# 10scm153adp1_io.net
KiCad netlist of a schematic drawn in Altium Designer
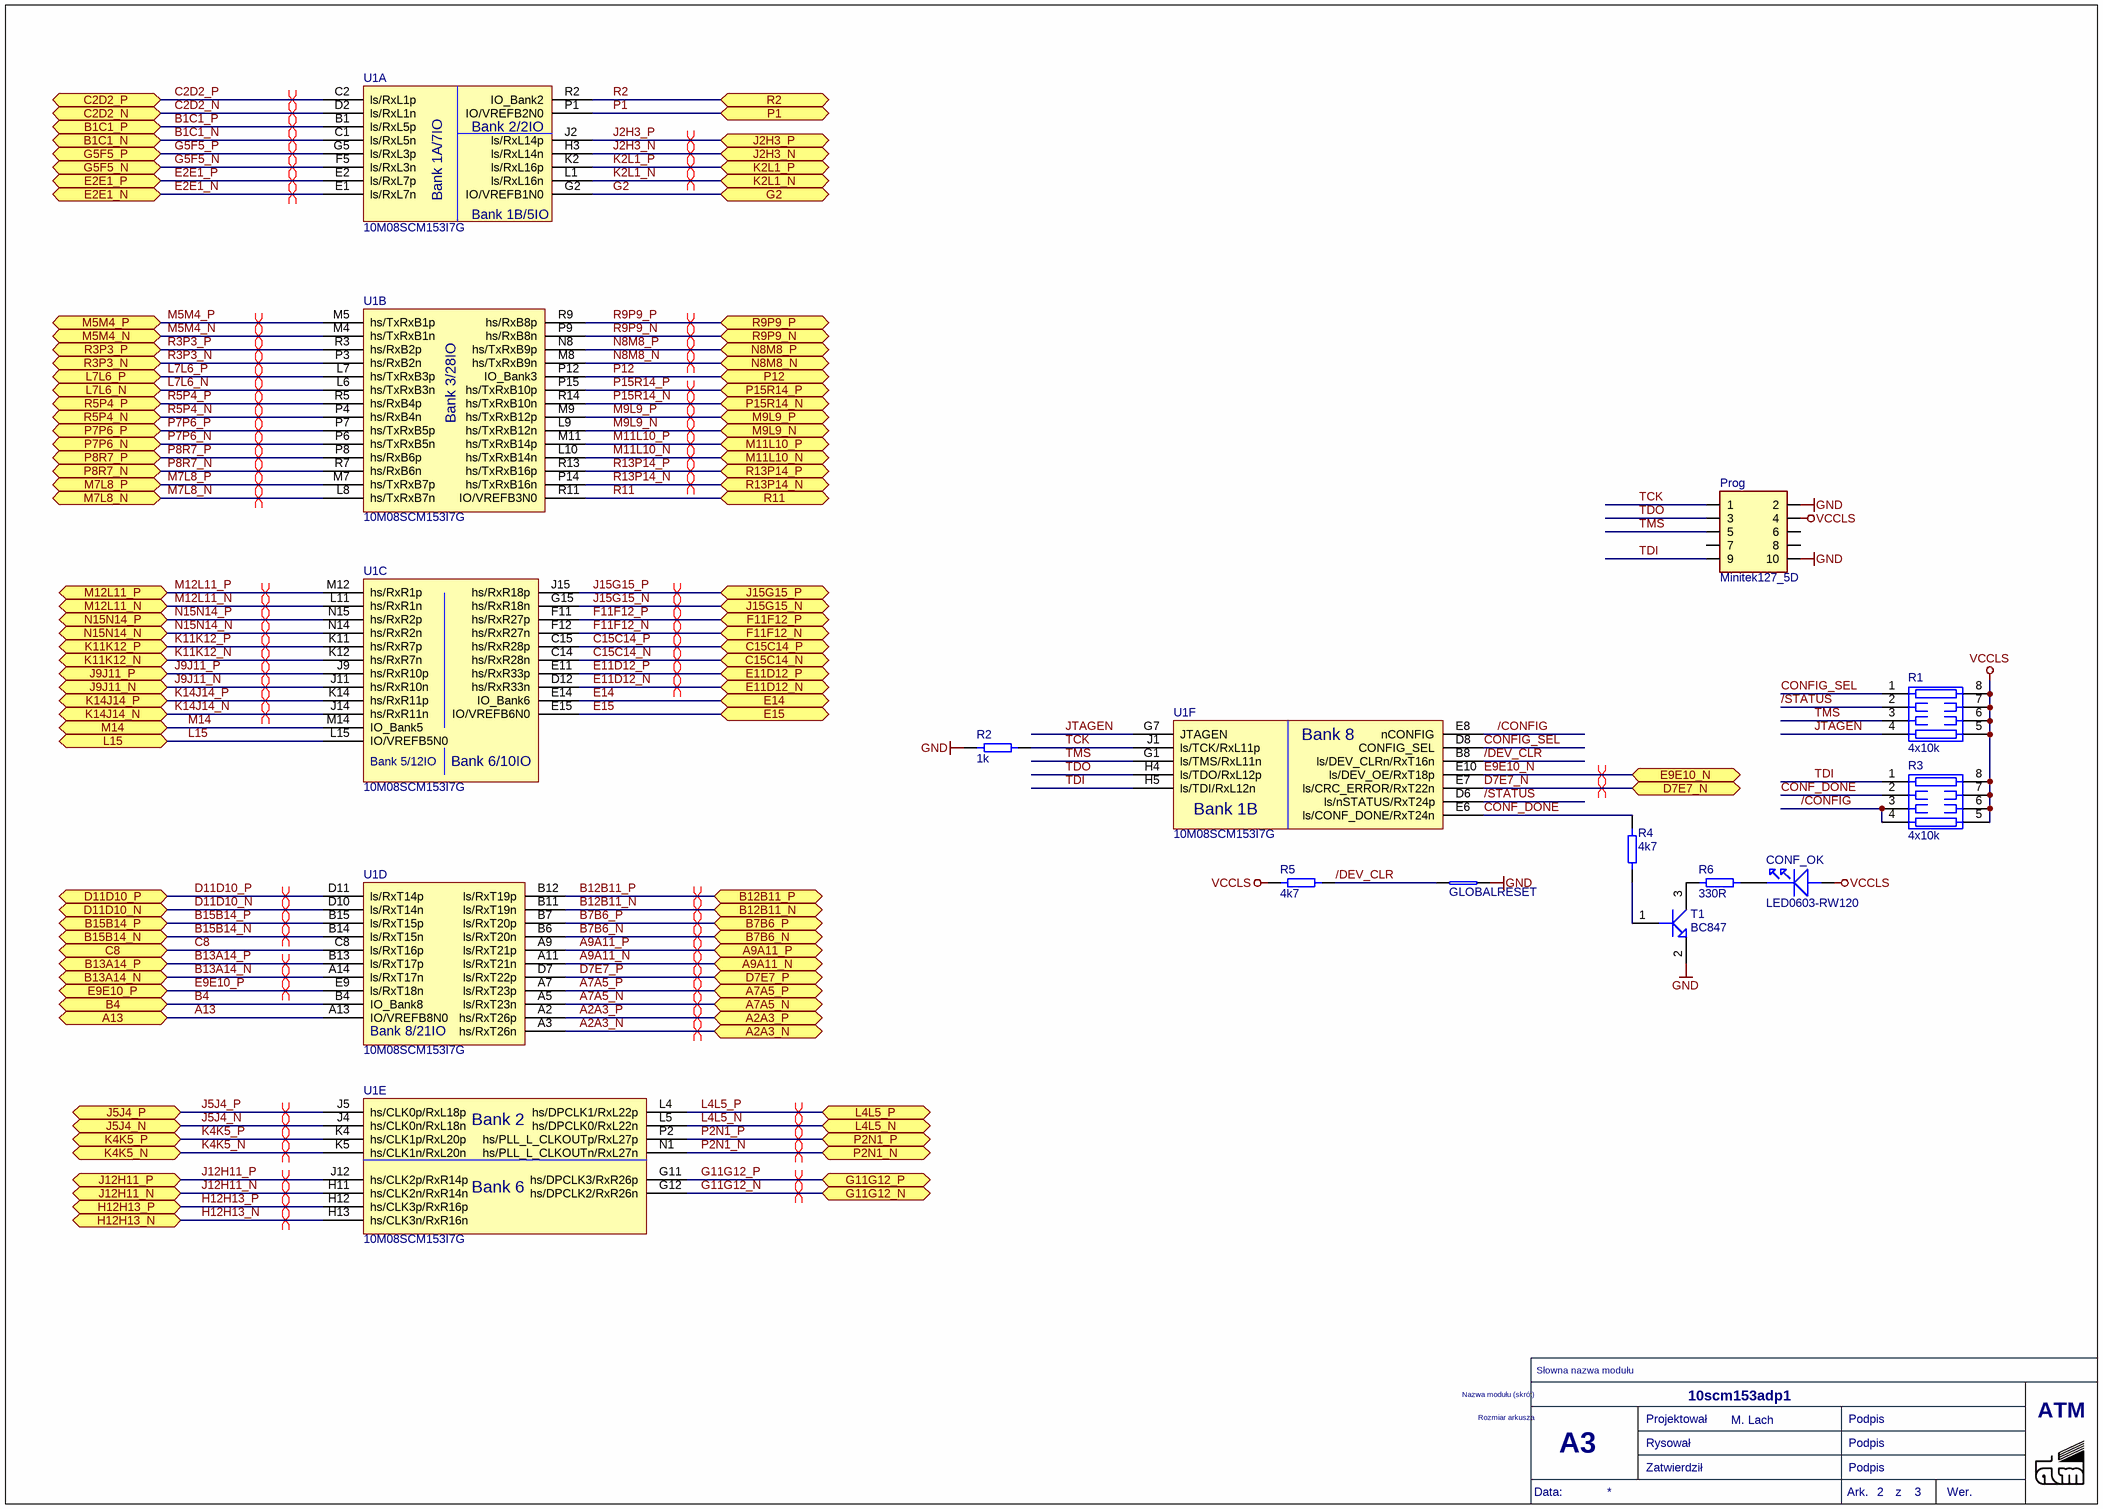
[diagram p0: 10scm153adp1_io.SchDoc]

(export (version "E")
  (design (tool "Eeschema 10.0.6"))
  (components
    (comp (ref "CONF_OK")
      (value "LED0603-RW120")
      (footprint "D0603")
      (libsource (lib "PartsMySQL") (part "LED"))
    )
    (comp (ref "GLOBALRESET")
      (value "SHORT0805")
      (footprint "SHORT0805")
      (libsource (lib "PartsMySQL") (part "SHORT"))
    )
    (comp (ref "Prog")
      (value "Minitek127_5D")
      (footprint "MINITEK127_5D")
      (libsource (lib "PartsMySQL") (part "HEADER5X2"))
    )
    (comp (ref "R1") (value "4x10k") (footprint "1206RP") (libsource (lib "PartsMySQL") (part "DR1206")))
    (comp (ref "R2") (value "1k") (footprint "0603R") (libsource (lib "PartsMySQL") (part "R")))
    (comp (ref "R3") (value "4x10k") (footprint "1206RP") (libsource (lib "PartsMySQL") (part "DR1206")))
    (comp (ref "R4") (value "4k7") (footprint "0603R") (libsource (lib "PartsMySQL") (part "R")))
    (comp (ref "R5") (value "4k7") (footprint "0603R") (libsource (lib "PartsMySQL") (part "R")))
    (comp (ref "R6") (value "330R") (footprint "0603R") (libsource (lib "PartsMySQL") (part "R")))
    (comp (ref "T1")
      (value "BC847")
      (footprint "SOT23-3")
      (libsource (lib "PartsMySQL") (part "NPN_SOT23-3"))
    )
    (comp (ref "U1")
      (value "10M08SCM153I7G")
      (footprint "MBGA153x15")
      (libsource (lib "PartsMySQL") (part "10M08SCM153"))
    )
  )
  (nets
    (net (code "1") (name "/A2A3_N") (class "Default")
      (node (ref "U1") (pin "A3") (pinfunction "hs/RxT26n_A3") (pintype "passive"))
    )
    (net (code "2") (name "/A2A3_P") (class "Default")
      (node (ref "U1") (pin "A2") (pinfunction "hs/RxT26p_A2") (pintype "passive"))
    )
    (net (code "3") (name "/A7A5_N") (class "Default")
      (node (ref "U1") (pin "A5") (pinfunction "ls/RxT23n_A5") (pintype "passive"))
    )
    (net (code "4") (name "/A7A5_P") (class "Default")
      (node (ref "U1") (pin "A7") (pinfunction "ls/RxT23p_A7") (pintype "passive"))
    )
    (net (code "5") (name "/A9A11_N") (class "Default")
      (node (ref "U1") (pin "A11") (pinfunction "ls/RxT21n_A11") (pintype "passive"))
    )
    (net (code "6") (name "/A9A11_P") (class "Default")
      (node (ref "U1") (pin "A9") (pinfunction "ls/RxT21p_A9") (pintype "passive"))
    )
    (net (code "7") (name "/A13") (class "Default")
      (node (ref "U1") (pin "A13") (pinfunction "IO/VREFB8N0_A13") (pintype "passive"))
    )
    (net (code "8") (name "/B1C1_N") (class "Default")
      (node (ref "U1") (pin "C1") (pinfunction "ls/RxL5n_C1") (pintype "passive"))
    )
    (net (code "9") (name "/B1C1_P") (class "Default")
      (node (ref "U1") (pin "B1") (pinfunction "ls/RxL5p_B1") (pintype "passive"))
    )
    (net (code "10") (name "/B4") (class "Default")
      (node (ref "U1") (pin "B4") (pinfunction "IO_Bank8_B4") (pintype "passive"))
    )
    (net (code "11") (name "/B7B6_N") (class "Default")
      (node (ref "U1") (pin "B6") (pinfunction "ls/RxT20n_B6") (pintype "passive"))
    )
    (net (code "12") (name "/B7B6_P") (class "Default")
      (node (ref "U1") (pin "B7") (pinfunction "ls/RxT20p_B7") (pintype "passive"))
    )
    (net (code "13") (name "/B12B11_N") (class "Default")
      (node (ref "U1") (pin "B11") (pinfunction "ls/RxT19n_B11") (pintype "passive"))
    )
    (net (code "14") (name "/B12B11_P") (class "Default")
      (node (ref "U1") (pin "B12") (pinfunction "ls/RxT19p_B12") (pintype "passive"))
    )
    (net (code "15") (name "/B13A14_N") (class "Default")
      (node (ref "U1") (pin "A14") (pinfunction "ls/RxT17n_A14") (pintype "passive"))
    )
    (net (code "16") (name "/B13A14_P") (class "Default")
      (node (ref "U1") (pin "B13") (pinfunction "ls/RxT17p_B13") (pintype "passive"))
    )
    (net (code "17") (name "/B15B14_N") (class "Default")
      (node (ref "U1") (pin "B14") (pinfunction "ls/RxT15n_B14") (pintype "passive"))
    )
    (net (code "18") (name "/B15B14_P") (class "Default")
      (node (ref "U1") (pin "B15") (pinfunction "ls/RxT15p_B15") (pintype "passive"))
    )
    (net (code "19") (name "/C2D2_N") (class "Default")
      (node (ref "U1") (pin "D2") (pinfunction "ls/RxL1n_D2") (pintype "passive"))
    )
    (net (code "20") (name "/C2D2_P") (class "Default")
      (node (ref "U1") (pin "C2") (pinfunction "ls/RxL1p_C2") (pintype "passive"))
    )
    (net (code "21") (name "/C8") (class "Default")
      (node (ref "U1") (pin "C8") (pinfunction "ls/RxT16p_C8") (pintype "passive"))
    )
    (net (code "22") (name "/C15C14_N") (class "Default")
      (node (ref "U1") (pin "C14") (pinfunction "hs/RxR28n_C14") (pintype "passive"))
    )
    (net (code "23") (name "/C15C14_P") (class "Default")
      (node (ref "U1") (pin "C15") (pinfunction "hs/RxR28p_C15") (pintype "passive"))
    )
    (net (code "24") (name "/CONFIG_SEL") (class "Default")
      (node (ref "R1") (pin "1") (pinfunction "R1_1") (pintype "passive"))
      (node (ref "U1") (pin "D8") (pinfunction "CONFIG_SEL_D8") (pintype "passive"))
    )
    (net (code "25") (name "/CONF_DONE") (class "Default")
      (node (ref "R3") (pin "2") (pinfunction "R2_2") (pintype "passive"))
      (node (ref "R4") (pin "1") (pinfunction "1_1") (pintype "passive"))
      (node (ref "U1") (pin "E6") (pinfunction "ls/CONF_DONE/RxT24n_E6") (pintype "passive"))
    )
    (net (code "26") (name "/D7E7_N") (class "Default")
      (node (ref "U1") (pin "E7") (pinfunction "ls/CRC_ERROR/RxT22n_E7") (pintype "passive"))
    )
    (net (code "27") (name "/D7E7_P") (class "Default")
      (node (ref "U1") (pin "D7") (pinfunction "ls/RxT22p_D7") (pintype "passive"))
    )
    (net (code "28") (name "/D11D10_N") (class "Default")
      (node (ref "U1") (pin "D10") (pinfunction "ls/RxT14n_D10") (pintype "passive"))
    )
    (net (code "29") (name "/D11D10_P") (class "Default")
      (node (ref "U1") (pin "D11") (pinfunction "ls/RxT14p_D11") (pintype "passive"))
    )
    (net (code "30") (name "/E2E1_N") (class "Default")
      (node (ref "U1") (pin "E1") (pinfunction "ls/RxL7n_E1") (pintype "passive"))
    )
    (net (code "31") (name "/E2E1_P") (class "Default")
      (node (ref "U1") (pin "E2") (pinfunction "ls/RxL7p_E2") (pintype "passive"))
    )
    (net (code "32") (name "/E9E10_N") (class "Default")
      (node (ref "U1") (pin "E10") (pinfunction "ls/DEV_OE/RxT18p_E10") (pintype "passive"))
    )
    (net (code "33") (name "/E9E10_P") (class "Default")
      (node (ref "U1") (pin "E9") (pinfunction "ls/RxT18n_E9") (pintype "passive"))
    )
    (net (code "34") (name "/E11D12_N") (class "Default")
      (node (ref "U1") (pin "D12") (pinfunction "hs/RxR33n_D12") (pintype "passive"))
    )
    (net (code "35") (name "/E11D12_P") (class "Default")
      (node (ref "U1") (pin "E11") (pinfunction "hs/RxR33p_E11") (pintype "passive"))
    )
    (net (code "36") (name "/E14") (class "Default")
      (node (ref "U1") (pin "E14") (pinfunction "IO_Bank6_E14") (pintype "passive"))
    )
    (net (code "37") (name "/E15") (class "Default")
      (node (ref "U1") (pin "E15") (pinfunction "IO/VREFB6N0_E15") (pintype "passive"))
    )
    (net (code "38") (name "/F11F12_N") (class "Default")
      (node (ref "U1") (pin "F12") (pinfunction "hs/RxR27n_F12") (pintype "passive"))
    )
    (net (code "39") (name "/F11F12_P") (class "Default")
      (node (ref "U1") (pin "F11") (pinfunction "hs/RxR27p_F11") (pintype "passive"))
    )
    (net (code "40") (name "/G2") (class "Default")
      (node (ref "U1") (pin "G2") (pinfunction "IO/VREFB1N0_G2") (pintype "passive"))
    )
    (net (code "41") (name "/G5F5_N") (class "Default")
      (node (ref "U1") (pin "F5") (pinfunction "ls/RxL3n_F5") (pintype "passive"))
    )
    (net (code "42") (name "/G5F5_P") (class "Default")
      (node (ref "U1") (pin "G5") (pinfunction "ls/RxL3p_G5") (pintype "passive"))
    )
    (net (code "43") (name "/G11G12_N") (class "Default")
      (node (ref "U1") (pin "G12") (pinfunction "hs/DPCLK2/RxR26n_G12") (pintype "passive"))
    )
    (net (code "44") (name "/G11G12_P") (class "Default")
      (node (ref "U1") (pin "G11") (pinfunction "hs/DPCLK3/RxR26p_G11") (pintype "passive"))
    )
    (net (code "45") (name "/H12H13_N") (class "Default")
      (node (ref "U1") (pin "H13") (pinfunction "hs/CLK3n/RxR16n_H13") (pintype "passive"))
    )
    (net (code "46") (name "/H12H13_P") (class "Default")
      (node (ref "U1") (pin "H12") (pinfunction "hs/CLK3p/RxR16p_H12") (pintype "passive"))
    )
    (net (code "47") (name "/J2H3_N") (class "Default")
      (node (ref "U1") (pin "H3") (pinfunction "ls/RxL14n_H3") (pintype "passive"))
    )
    (net (code "48") (name "/J2H3_P") (class "Default")
      (node (ref "U1") (pin "J2") (pinfunction "ls/RxL14p_J2") (pintype "passive"))
    )
    (net (code "49") (name "/J5J4_N") (class "Default")
      (node (ref "U1") (pin "J4") (pinfunction "hs/CLK0n/RxL18n_J4") (pintype "passive"))
    )
    (net (code "50") (name "/J5J4_P") (class "Default")
      (node (ref "U1") (pin "J5") (pinfunction "hs/CLK0p/RxL18p_J5") (pintype "passive"))
    )
    (net (code "51") (name "/J9J11_N") (class "Default")
      (node (ref "U1") (pin "J11") (pinfunction "hs/RxR10n_J11") (pintype "passive"))
    )
    (net (code "52") (name "/J9J11_P") (class "Default")
      (node (ref "U1") (pin "J9") (pinfunction "hs/RxR10p_J9") (pintype "passive"))
    )
    (net (code "53") (name "/J12H11_N") (class "Default")
      (node (ref "U1") (pin "H11") (pinfunction "hs/CLK2n/RxR14n_H11") (pintype "passive"))
    )
    (net (code "54") (name "/J12H11_P") (class "Default")
      (node (ref "U1") (pin "J12") (pinfunction "hs/CLK2p/RxR14p_J12") (pintype "passive"))
    )
    (net (code "55") (name "/J15G15_N") (class "Default")
      (node (ref "U1") (pin "G15") (pinfunction "hs/RxR18n_G15") (pintype "passive"))
    )
    (net (code "56") (name "/J15G15_P") (class "Default")
      (node (ref "U1") (pin "J15") (pinfunction "hs/RxR18p_J15") (pintype "passive"))
    )
    (net (code "57") (name "/JTAGEN") (class "Default")
      (node (ref "R1") (pin "4") (pinfunction "R4_4") (pintype "passive"))
      (node (ref "U1") (pin "G7") (pinfunction "JTAGEN_G7") (pintype "passive"))
    )
    (net (code "58") (name "/K2L1_N") (class "Default")
      (node (ref "U1") (pin "L1") (pinfunction "ls/RxL16n_L1") (pintype "passive"))
    )
    (net (code "59") (name "/K2L1_P") (class "Default")
      (node (ref "U1") (pin "K2") (pinfunction "ls/RxL16p_K2") (pintype "passive"))
    )
    (net (code "60") (name "/K4K5_N") (class "Default")
      (node (ref "U1") (pin "K5") (pinfunction "hs/CLK1n/RxL20n_K5") (pintype "passive"))
    )
    (net (code "61") (name "/K4K5_P") (class "Default")
      (node (ref "U1") (pin "K4") (pinfunction "hs/CLK1p/RxL20p_K4") (pintype "passive"))
    )
    (net (code "62") (name "/K11K12_N") (class "Default")
      (node (ref "U1") (pin "K12") (pinfunction "hs/RxR7n_K12") (pintype "passive"))
    )
    (net (code "63") (name "/K11K12_P") (class "Default")
      (node (ref "U1") (pin "K11") (pinfunction "hs/RxR7p_K11") (pintype "passive"))
    )
    (net (code "64") (name "/K14J14_N") (class "Default")
      (node (ref "U1") (pin "J14") (pinfunction "hs/RxR11n_J14") (pintype "passive"))
    )
    (net (code "65") (name "/K14J14_P") (class "Default")
      (node (ref "U1") (pin "K14") (pinfunction "hs/RxR11p_K14") (pintype "passive"))
    )
    (net (code "66") (name "/L4L5_N") (class "Default")
      (node (ref "U1") (pin "L5") (pinfunction "hs/DPCLK0/RxL22n_L5") (pintype "passive"))
    )
    (net (code "67") (name "/L4L5_P") (class "Default")
      (node (ref "U1") (pin "L4") (pinfunction "hs/DPCLK1/RxL22p_L4") (pintype "passive"))
    )
    (net (code "68") (name "/L7L6_N") (class "Default")
      (node (ref "U1") (pin "L6") (pinfunction "hs/TxRxB3n_L6") (pintype "passive"))
    )
    (net (code "69") (name "/L7L6_P") (class "Default")
      (node (ref "U1") (pin "L7") (pinfunction "hs/TxRxB3p_L7") (pintype "passive"))
    )
    (net (code "70") (name "/L15") (class "Default")
      (node (ref "U1") (pin "L15") (pinfunction "IO/VREFB5N0_L15") (pintype "passive"))
    )
    (net (code "71") (name "/M5M4_N") (class "Default")
      (node (ref "U1") (pin "M4") (pinfunction "hs/TxRxB1n_M4") (pintype "passive"))
    )
    (net (code "72") (name "/M5M4_P") (class "Default")
      (node (ref "U1") (pin "M5") (pinfunction "hs/TxRxB1p_M5") (pintype "passive"))
    )
    (net (code "73") (name "/M7L8_N") (class "Default")
      (node (ref "U1") (pin "L8") (pinfunction "hs/TxRxB7n_L8") (pintype "passive"))
    )
    (net (code "74") (name "/M7L8_P") (class "Default")
      (node (ref "U1") (pin "M7") (pinfunction "hs/TxRxB7p_M7") (pintype "passive"))
    )
    (net (code "75") (name "/M9L9_N") (class "Default")
      (node (ref "U1") (pin "L9") (pinfunction "hs/TxRxB12n_L9") (pintype "passive"))
    )
    (net (code "76") (name "/M9L9_P") (class "Default")
      (node (ref "U1") (pin "M9") (pinfunction "hs/TxRxB12p_M9") (pintype "passive"))
    )
    (net (code "77") (name "/M11L10_N") (class "Default")
      (node (ref "U1") (pin "L10") (pinfunction "hs/TxRxB14n_L10") (pintype "passive"))
    )
    (net (code "78") (name "/M11L10_P") (class "Default")
      (node (ref "U1") (pin "M11") (pinfunction "hs/TxRxB14p_M11") (pintype "passive"))
    )
    (net (code "79") (name "/M12L11_N") (class "Default")
      (node (ref "U1") (pin "L11") (pinfunction "hs/RxR1n_L11") (pintype "passive"))
    )
    (net (code "80") (name "/M12L11_P") (class "Default")
      (node (ref "U1") (pin "M12") (pinfunction "hs/RxR1p_M12") (pintype "passive"))
    )
    (net (code "81") (name "/M14") (class "Default")
      (node (ref "U1") (pin "M14") (pinfunction "IO_Bank5_M14") (pintype "passive"))
    )
    (net (code "82") (name "/N8M8_N") (class "Default")
      (node (ref "U1") (pin "M8") (pinfunction "hs/TxRxB9n_M8") (pintype "passive"))
    )
    (net (code "83") (name "/N8M8_P") (class "Default")
      (node (ref "U1") (pin "N8") (pinfunction "hs/TxRxB9p_N8") (pintype "passive"))
    )
    (net (code "84") (name "/N15N14_N") (class "Default")
      (node (ref "U1") (pin "N14") (pinfunction "hs/RxR2n_N14") (pintype "passive"))
    )
    (net (code "85") (name "/N15N14_P") (class "Default")
      (node (ref "U1") (pin "N15") (pinfunction "hs/RxR2p_N15") (pintype "passive"))
    )
    (net (code "86") (name "/P1") (class "Default")
      (node (ref "U1") (pin "P1") (pinfunction "IO/VREFB2N0_P1") (pintype "passive"))
    )
    (net (code "87") (name "/P2N1_N") (class "Default")
      (node (ref "U1") (pin "N1") (pinfunction "hs/PLL_L_CLKOUTn/RxL27n_N1") (pintype "passive"))
    )
    (net (code "88") (name "/P2N1_P") (class "Default")
      (node (ref "U1") (pin "P2") (pinfunction "hs/PLL_L_CLKOUTp/RxL27p_P2") (pintype "passive"))
    )
    (net (code "89") (name "/P7P6_N") (class "Default")
      (node (ref "U1") (pin "P6") (pinfunction "hs/TxRxB5n_P6") (pintype "passive"))
    )
    (net (code "90") (name "/P7P6_P") (class "Default")
      (node (ref "U1") (pin "P7") (pinfunction "hs/TxRxB5p_P7") (pintype "passive"))
    )
    (net (code "91") (name "/P8R7_N") (class "Default")
      (node (ref "U1") (pin "R7") (pinfunction "hs/RxB6n_R7") (pintype "passive"))
    )
    (net (code "92") (name "/P8R7_P") (class "Default")
      (node (ref "U1") (pin "P8") (pinfunction "hs/RxB6p_P8") (pintype "passive"))
    )
    (net (code "93") (name "/P12") (class "Default")
      (node (ref "U1") (pin "P12") (pinfunction "IO_Bank3_P12") (pintype "passive"))
    )
    (net (code "94") (name "/P15R14_N") (class "Default")
      (node (ref "U1") (pin "R14") (pinfunction "hs/TxRxB10n_R14") (pintype "passive"))
    )
    (net (code "95") (name "/P15R14_P") (class "Default")
      (node (ref "U1") (pin "P15") (pinfunction "hs/TxRxB10p_P15") (pintype "passive"))
    )
    (net (code "96") (name "/R2") (class "Default")
      (node (ref "U1") (pin "R2") (pinfunction "IO_Bank2_R2") (pintype "passive"))
    )
    (net (code "97") (name "/R3P3_N") (class "Default")
      (node (ref "U1") (pin "P3") (pinfunction "hs/RxB2n_P3") (pintype "passive"))
    )
    (net (code "98") (name "/R3P3_P") (class "Default")
      (node (ref "U1") (pin "R3") (pinfunction "hs/RxB2p_R3") (pintype "passive"))
    )
    (net (code "99") (name "/R5P4_N") (class "Default")
      (node (ref "U1") (pin "P4") (pinfunction "hs/RxB4n_P4") (pintype "passive"))
    )
    (net (code "100") (name "/R5P4_P") (class "Default")
      (node (ref "U1") (pin "R5") (pinfunction "hs/RxB4p_R5") (pintype "passive"))
    )
    (net (code "101") (name "/R9P9_N") (class "Default")
      (node (ref "U1") (pin "P9") (pinfunction "hs/RxB8n_P9") (pintype "passive"))
    )
    (net (code "102") (name "/R9P9_P") (class "Default")
      (node (ref "U1") (pin "R9") (pinfunction "hs/RxB8p_R9") (pintype "passive"))
    )
    (net (code "103") (name "/R11") (class "Default")
      (node (ref "U1") (pin "R11") (pinfunction "IO/VREFB3N0_R11") (pintype "passive"))
    )
    (net (code "104") (name "/R13P14_N") (class "Default")
      (node (ref "U1") (pin "P14") (pinfunction "hs/TxRxB16n_P14") (pintype "passive"))
    )
    (net (code "105") (name "/R13P14_P") (class "Default")
      (node (ref "U1") (pin "R13") (pinfunction "hs/TxRxB16p_R13") (pintype "passive"))
    )
    (net (code "106") (name "/TCK") (class "Default")
      (node (ref "Prog") (pin "1") (pinfunction "1_1") (pintype "passive"))
      (node (ref "R2") (pin "2") (pinfunction "2_2") (pintype "passive"))
      (node (ref "U1") (pin "J1") (pinfunction "ls/TCK/RxL11p_J1") (pintype "passive"))
    )
    (net (code "107") (name "/TDI") (class "Default")
      (node (ref "Prog") (pin "9") (pinfunction "9_9") (pintype "passive"))
      (node (ref "R3") (pin "1") (pinfunction "R1_1") (pintype "passive"))
      (node (ref "U1") (pin "H5") (pinfunction "ls/TDI/RxL12n_H5") (pintype "passive"))
    )
    (net (code "108") (name "/TDO") (class "Default")
      (node (ref "Prog") (pin "3") (pinfunction "3_3") (pintype "passive"))
      (node (ref "U1") (pin "H4") (pinfunction "ls/TDO/RxL12p_H4") (pintype "passive"))
    )
    (net (code "109") (name "/TMS") (class "Default")
      (node (ref "Prog") (pin "5") (pinfunction "5_5") (pintype "passive"))
      (node (ref "R1") (pin "3") (pinfunction "R3_3") (pintype "passive"))
      (node (ref "U1") (pin "G1") (pinfunction "ls/TMS/RxL11n_G1") (pintype "passive"))
    )
    (net (code "110") (name "/{slash}CONFIG") (class "Default")
      (node (ref "R3") (pin "3") (pinfunction "R3_3") (pintype "passive"))
      (node (ref "R3") (pin "4") (pinfunction "R4_4") (pintype "passive"))
      (node (ref "U1") (pin "E8") (pinfunction "nCONFIG_E8") (pintype "passive"))
    )
    (net (code "111") (name "/{slash}DEV_CLR") (class "Default")
      (node (ref "GLOBALRESET") (pin "1") (pinfunction "1_1") (pintype "passive"))
      (node (ref "R5") (pin "1") (pinfunction "1_1") (pintype "passive"))
      (node (ref "U1") (pin "B8") (pinfunction "ls/DEV_CLRn/RxT16n_B8") (pintype "passive"))
    )
    (net (code "112") (name "/{slash}STATUS") (class "Default")
      (node (ref "R1") (pin "2") (pinfunction "R2_2") (pintype "passive"))
      (node (ref "U1") (pin "D6") (pinfunction "ls/nSTATUS/RxT24p_D6") (pintype "passive"))
    )
    (net (code "113") (name "GND") (class "Default")
      (node (ref "GLOBALRESET") (pin "2") (pinfunction "2_2") (pintype "passive"))
      (node (ref "Prog") (pin "10") (pinfunction "10_10") (pintype "passive"))
      (node (ref "Prog") (pin "2") (pinfunction "2_2") (pintype "passive"))
      (node (ref "R2") (pin "1") (pinfunction "1_1") (pintype "passive"))
      (node (ref "T1") (pin "2") (pinfunction "2_2") (pintype "passive"))
    )
    (net (code "114") (name "Net-(CONF_OK-PadCATH)") (class "Default")
      (node (ref "CONF_OK") (pin "CATH") (pinfunction "CATH_CATH") (pintype "passive"))
      (node (ref "R6") (pin "2") (pinfunction "2_2") (pintype "passive"))
    )
    (net (code "115") (name "Net-(R4-Pad2)") (class "Default")
      (node (ref "R4") (pin "2") (pinfunction "2_2") (pintype "passive"))
      (node (ref "T1") (pin "1") (pinfunction "1_1") (pintype "passive"))
    )
    (net (code "116") (name "Net-(R6-Pad1)") (class "Default")
      (node (ref "R6") (pin "1") (pinfunction "1_1") (pintype "passive"))
      (node (ref "T1") (pin "3") (pinfunction "3_3") (pintype "passive"))
    )
    (net (code "117") (name "VCCLS") (class "Default")
      (node (ref "CONF_OK") (pin "ANOD") (pinfunction "ANOD_ANOD") (pintype "passive"))
      (node (ref "Prog") (pin "4") (pinfunction "4_4") (pintype "passive"))
      (node (ref "R1") (pin "5") (pinfunction "R5_5") (pintype "passive"))
      (node (ref "R1") (pin "6") (pinfunction "R6_6") (pintype "passive"))
      (node (ref "R1") (pin "7") (pinfunction "R7_7") (pintype "passive"))
      (node (ref "R1") (pin "8") (pinfunction "R8_8") (pintype "passive"))
      (node (ref "R3") (pin "5") (pinfunction "R5_5") (pintype "passive"))
      (node (ref "R3") (pin "6") (pinfunction "R6_6") (pintype "passive"))
      (node (ref "R3") (pin "7") (pinfunction "R7_7") (pintype "passive"))
      (node (ref "R3") (pin "8") (pinfunction "R8_8") (pintype "passive"))
      (node (ref "R5") (pin "2") (pinfunction "2_2") (pintype "passive"))
    )
    (net (code "118") (name "unconnected-(Prog-Pad6)") (class "Default")
      (node (ref "Prog") (pin "6") (pinfunction "6_6") (pintype "passive"))
    )
    (net (code "119") (name "unconnected-(Prog-Pad7)") (class "Default")
      (node (ref "Prog") (pin "7") (pinfunction "7_7") (pintype "passive"))
    )
    (net (code "120") (name "unconnected-(Prog-Pad8)") (class "Default")
      (node (ref "Prog") (pin "8") (pinfunction "8_8") (pintype "passive"))
    )
  )
)
